# Power-Conversion.net
KiCad netlist of a schematic drawn in EAGLE
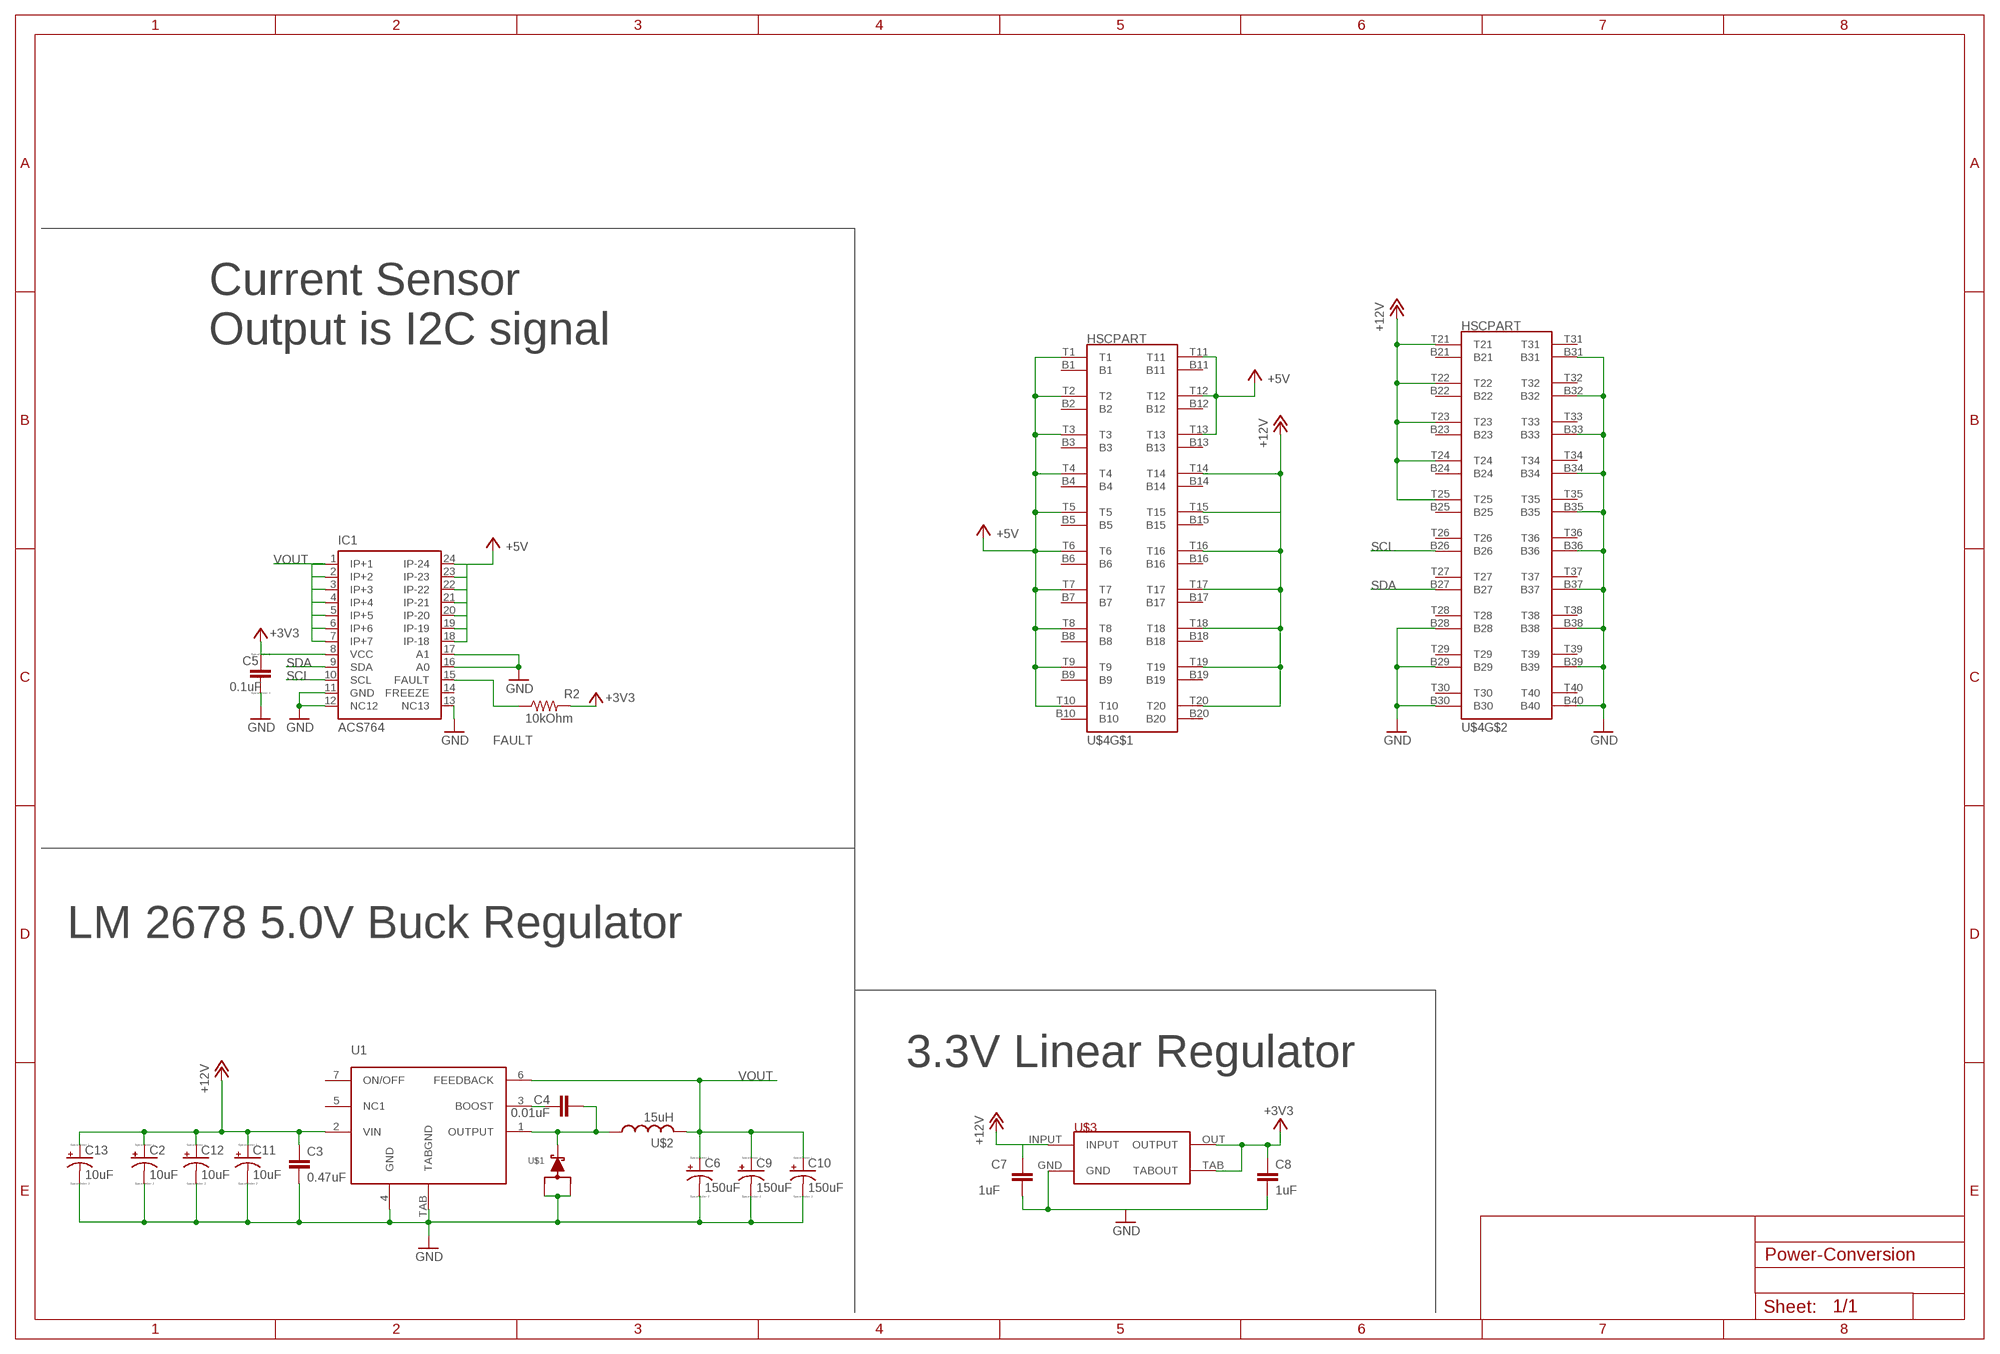
[diagram p0: schematic, sheet 1]

(export (version "E")
  (design (tool "Eeschema 10.0.6"))
  (components
    (comp (ref "C2")
      (value "10uF")
      (footprint "eagle-import:CTAN(7.30_4.30MM)")
      (libsource (lib "eagle-import") (part "C-TANTALUM(10UF_150UF)"))
    )
    (comp (ref "C3")
      (value "0.47uF")
      (footprint "eagle-import:0805")
      (libsource (lib "eagle-import") (part "CAP0805"))
    )
    (comp (ref "C4")
      (value "0.01uF")
      (footprint "eagle-import:0603-CAP")
      (libsource (lib "eagle-import") (part "SparkFun-Passives_CAP0603-CAP"))
    )
    (comp (ref "C5")
      (value "0.1uF")
      (footprint "eagle-import:C0603")
      (libsource (lib "eagle-import") (part "CC0603"))
    )
    (comp (ref "C6")
      (value "150uF")
      (footprint "eagle-import:CTAN(7.30_4.30MM)")
      (libsource (lib "eagle-import") (part "C-TANTALUM(10UF_150UF)"))
    )
    (comp (ref "C7")
      (value "1uF")
      (footprint "eagle-import:0603-CAP")
      (libsource (lib "eagle-import") (part "SparkFun-Passives_CAP0603-CAP"))
    )
    (comp (ref "C8")
      (value "1uF")
      (footprint "eagle-import:0603-CAP")
      (libsource (lib "eagle-import") (part "SparkFun-Passives_CAP0603-CAP"))
    )
    (comp (ref "C9")
      (value "150uF")
      (footprint "eagle-import:CTAN(7.30_4.30MM)")
      (libsource (lib "eagle-import") (part "C-TANTALUM(10UF_150UF)"))
    )
    (comp (ref "C10")
      (value "150uF")
      (footprint "eagle-import:CTAN(7.30_4.30MM)")
      (libsource (lib "eagle-import") (part "C-TANTALUM(10UF_150UF)"))
    )
    (comp (ref "C11")
      (value "10uF")
      (footprint "eagle-import:CTAN(7.30_4.30MM)")
      (libsource (lib "eagle-import") (part "C-TANTALUM(10UF_150UF)"))
    )
    (comp (ref "C12")
      (value "10uF")
      (footprint "eagle-import:CTAN(7.30_4.30MM)")
      (libsource (lib "eagle-import") (part "C-TANTALUM(10UF_150UF)"))
    )
    (comp (ref "C13")
      (value "10uF")
      (footprint "eagle-import:CTAN(7.30_4.30MM)")
      (libsource (lib "eagle-import") (part "C-TANTALUM(10UF_150UF)"))
    )
    (comp (ref "IC1")
      (value "ACS764")
      (footprint "eagle-import:SSOP24")
      (libsource (lib "eagle-import") (part "ACS764"))
    )
    (comp (ref "R2")
      (value "10kOhm")
      (footprint "eagle-import:R0603")
      (libsource (lib "eagle-import") (part "R-US_R0603"))
    )
    (comp (ref "U$1")
      (value "SWITCHMODE_SCHOTTKY")
      (footprint "eagle-import:DPAK-3")
      (libsource (lib "eagle-import") (part "SWITCHMODE_SCHOTTKY"))
    )
    (comp (ref "U$2")
      (value "15uH")
      (footprint "eagle-import:HCMA1305")
      (libsource (lib "eagle-import") (part "HCMA1305"))
    )
    (comp (ref "U$3")
      (value "NCP1117")
      (footprint "eagle-import:NCP1117")
      (libsource (lib "eagle-import") (part "NCP1117"))
    )
    (comp (ref "U$4")
      (value "HSCPART")
      (footprint "eagle-import:HSC8-40PINOUUT")
      (libsource (lib "eagle-import") (part "HSCPART"))
    )
    (comp (ref "U1")
      (value "LM2678")
      (footprint "eagle-import:LM2678")
      (libsource (lib "eagle-import") (part "LM2678"))
    )
  )
  (nets
    (net (code "1") (name "+3V3") (class "Default")
      (node (ref "C5") (pin "1") (pinfunction "1_1") (pintype "passive"))
      (node (ref "C8") (pin "1") (pinfunction "1_1") (pintype "passive"))
      (node (ref "IC1") (pin "8") (pinfunction "VCC_8") (pintype "bidirectional"))
      (node (ref "R2") (pin "2") (pinfunction "2_2") (pintype "passive"))
      (node (ref "U$3") (pin "OUT") (pinfunction "OUTPUT_OUT") (pintype "bidirectional"))
      (node (ref "U$3") (pin "TAB") (pinfunction "TABOUT_TAB") (pintype "bidirectional"))
    )
    (net (code "2") (name "+5V") (class "Default")
      (node (ref "IC1") (pin "18") (pinfunction "IP-18_18") (pintype "bidirectional"))
      (node (ref "IC1") (pin "19") (pinfunction "IP-19_19") (pintype "bidirectional"))
      (node (ref "IC1") (pin "20") (pinfunction "IP-20_20") (pintype "bidirectional"))
      (node (ref "IC1") (pin "21") (pinfunction "IP-21_21") (pintype "bidirectional"))
      (node (ref "IC1") (pin "22") (pinfunction "IP-22_22") (pintype "bidirectional"))
      (node (ref "IC1") (pin "23") (pinfunction "IP-23_23") (pintype "bidirectional"))
      (node (ref "IC1") (pin "24") (pinfunction "IP-24_24") (pintype "bidirectional"))
      (node (ref "U$4") (pin "T1") (pinfunction "T1_T1") (pintype "bidirectional"))
      (node (ref "U$4") (pin "T10") (pinfunction "T10_T10") (pintype "bidirectional"))
      (node (ref "U$4") (pin "T11") (pinfunction "T11_T11") (pintype "bidirectional"))
      (node (ref "U$4") (pin "T12") (pinfunction "T12_T12") (pintype "bidirectional"))
      (node (ref "U$4") (pin "T13") (pinfunction "T13_T13") (pintype "bidirectional"))
      (node (ref "U$4") (pin "T2") (pinfunction "T2_T2") (pintype "bidirectional"))
      (node (ref "U$4") (pin "T3") (pinfunction "T3_T3") (pintype "bidirectional"))
      (node (ref "U$4") (pin "T4") (pinfunction "T4_T4") (pintype "bidirectional"))
      (node (ref "U$4") (pin "T5") (pinfunction "T5_T5") (pintype "bidirectional"))
      (node (ref "U$4") (pin "T6") (pinfunction "T6_T6") (pintype "bidirectional"))
      (node (ref "U$4") (pin "T7") (pinfunction "T7_T7") (pintype "bidirectional"))
      (node (ref "U$4") (pin "T8") (pinfunction "T8_T8") (pintype "bidirectional"))
      (node (ref "U$4") (pin "T9") (pinfunction "T9_T9") (pintype "bidirectional"))
    )
    (net (code "3") (name "+12V") (class "Default")
      (node (ref "C11") (pin "+") (pinfunction "+_+") (pintype "passive"))
      (node (ref "C12") (pin "+") (pinfunction "+_+") (pintype "passive"))
      (node (ref "C13") (pin "+") (pinfunction "+_+") (pintype "passive"))
      (node (ref "C2") (pin "+") (pinfunction "+_+") (pintype "passive"))
      (node (ref "C3") (pin "1") (pinfunction "1_1") (pintype "passive"))
      (node (ref "C7") (pin "1") (pinfunction "1_1") (pintype "passive"))
      (node (ref "U$3") (pin "INPUT") (pinfunction "INPUT_INPUT") (pintype "bidirectional"))
      (node (ref "U$4") (pin "T14") (pinfunction "T14_T14") (pintype "bidirectional"))
      (node (ref "U$4") (pin "T15") (pinfunction "T15_T15") (pintype "bidirectional"))
      (node (ref "U$4") (pin "T16") (pinfunction "T16_T16") (pintype "bidirectional"))
      (node (ref "U$4") (pin "T17") (pinfunction "T17_T17") (pintype "bidirectional"))
      (node (ref "U$4") (pin "T18") (pinfunction "T18_T18") (pintype "bidirectional"))
      (node (ref "U$4") (pin "T19") (pinfunction "T19_T19") (pintype "bidirectional"))
      (node (ref "U$4") (pin "T20") (pinfunction "T20_T20") (pintype "bidirectional"))
      (node (ref "U$4") (pin "T21") (pinfunction "T21_T21") (pintype "bidirectional"))
      (node (ref "U$4") (pin "T22") (pinfunction "T22_T22") (pintype "bidirectional"))
      (node (ref "U$4") (pin "T23") (pinfunction "T23_T23") (pintype "bidirectional"))
      (node (ref "U$4") (pin "T24") (pinfunction "T24_T24") (pintype "bidirectional"))
      (node (ref "U$4") (pin "T25") (pinfunction "T25_T25") (pintype "bidirectional"))
      (node (ref "U1") (pin "2") (pinfunction "VIN_2") (pintype "bidirectional"))
    )
    (net (code "4") (name "/FAULT") (class "Default")
      (node (ref "IC1") (pin "15") (pinfunction "FAULT_15") (pintype "bidirectional"))
      (node (ref "R2") (pin "1") (pinfunction "1_1") (pintype "passive"))
    )
    (net (code "5") (name "/SCL") (class "Default")
      (node (ref "IC1") (pin "10") (pinfunction "SCL_10") (pintype "bidirectional"))
      (node (ref "U$4") (pin "B26") (pinfunction "B26_B26") (pintype "bidirectional"))
    )
    (net (code "6") (name "/SDA") (class "Default")
      (node (ref "IC1") (pin "9") (pinfunction "SDA_9") (pintype "bidirectional"))
      (node (ref "U$4") (pin "B27") (pinfunction "B27_B27") (pintype "bidirectional"))
    )
    (net (code "7") (name "/VOUT") (class "Default")
      (node (ref "C10") (pin "+") (pinfunction "+_+") (pintype "passive"))
      (node (ref "C6") (pin "+") (pinfunction "+_+") (pintype "passive"))
      (node (ref "C9") (pin "+") (pinfunction "+_+") (pintype "passive"))
      (node (ref "IC1") (pin "1") (pinfunction "IP+1_1") (pintype "bidirectional"))
      (node (ref "IC1") (pin "2") (pinfunction "IP+2_2") (pintype "bidirectional"))
      (node (ref "IC1") (pin "3") (pinfunction "IP+3_3") (pintype "bidirectional"))
      (node (ref "IC1") (pin "4") (pinfunction "IP+4_4") (pintype "bidirectional"))
      (node (ref "IC1") (pin "5") (pinfunction "IP+5_5") (pintype "bidirectional"))
      (node (ref "IC1") (pin "6") (pinfunction "IP+6_6") (pintype "bidirectional"))
      (node (ref "IC1") (pin "7") (pinfunction "IP+7_7") (pintype "bidirectional"))
      (node (ref "U$2") (pin "P$2") (pinfunction "2_P$2") (pintype "passive"))
      (node (ref "U1") (pin "6") (pinfunction "FEEDBACK_6") (pintype "bidirectional"))
    )
    (net (code "8") (name "GND") (class "Default")
      (node (ref "C10") (pin "-") (pinfunction "-_-") (pintype "passive"))
      (node (ref "C11") (pin "-") (pinfunction "-_-") (pintype "passive"))
      (node (ref "C12") (pin "-") (pinfunction "-_-") (pintype "passive"))
      (node (ref "C13") (pin "-") (pinfunction "-_-") (pintype "passive"))
      (node (ref "C2") (pin "-") (pinfunction "-_-") (pintype "passive"))
      (node (ref "C3") (pin "2") (pinfunction "2_2") (pintype "passive"))
      (node (ref "C5") (pin "2") (pinfunction "2_2") (pintype "passive"))
      (node (ref "C6") (pin "-") (pinfunction "-_-") (pintype "passive"))
      (node (ref "C7") (pin "2") (pinfunction "2_2") (pintype "passive"))
      (node (ref "C8") (pin "2") (pinfunction "2_2") (pintype "passive"))
      (node (ref "C9") (pin "-") (pinfunction "-_-") (pintype "passive"))
      (node (ref "IC1") (pin "11") (pinfunction "GND_11") (pintype "bidirectional"))
      (node (ref "IC1") (pin "12") (pinfunction "NC12_12") (pintype "bidirectional"))
      (node (ref "IC1") (pin "13") (pinfunction "NC13_13") (pintype "bidirectional"))
      (node (ref "IC1") (pin "16") (pinfunction "A0_16") (pintype "bidirectional"))
      (node (ref "IC1") (pin "17") (pinfunction "A1_17") (pintype "bidirectional"))
      (node (ref "U$1") (pin "P$1") (pinfunction "P$1_P$1") (pintype "bidirectional"))
      (node (ref "U$1") (pin "P$3") (pinfunction "P$3_P$3") (pintype "bidirectional"))
      (node (ref "U$3") (pin "GND") (pinfunction "GND_GND") (pintype "bidirectional"))
      (node (ref "U$4") (pin "B28") (pinfunction "B28_B28") (pintype "bidirectional"))
      (node (ref "U$4") (pin "B29") (pinfunction "B29_B29") (pintype "bidirectional"))
      (node (ref "U$4") (pin "B30") (pinfunction "B30_B30") (pintype "bidirectional"))
      (node (ref "U$4") (pin "B31") (pinfunction "B31_B31") (pintype "bidirectional"))
      (node (ref "U$4") (pin "B32") (pinfunction "B32_B32") (pintype "bidirectional"))
      (node (ref "U$4") (pin "B33") (pinfunction "B33_B33") (pintype "bidirectional"))
      (node (ref "U$4") (pin "B34") (pinfunction "B34_B34") (pintype "bidirectional"))
      (node (ref "U$4") (pin "B35") (pinfunction "B35_B35") (pintype "bidirectional"))
      (node (ref "U$4") (pin "B36") (pinfunction "B36_B36") (pintype "bidirectional"))
      (node (ref "U$4") (pin "B37") (pinfunction "B37_B37") (pintype "bidirectional"))
      (node (ref "U$4") (pin "B38") (pinfunction "B38_B38") (pintype "bidirectional"))
      (node (ref "U$4") (pin "B39") (pinfunction "B39_B39") (pintype "bidirectional"))
      (node (ref "U$4") (pin "B40") (pinfunction "B40_B40") (pintype "bidirectional"))
      (node (ref "U1") (pin "4") (pinfunction "GND_4") (pintype "bidirectional"))
      (node (ref "U1") (pin "TAB") (pinfunction "TABGND_TAB") (pintype "bidirectional"))
    )
    (net (code "9") (name "Net-(U$2-1)") (class "Default")
      (node (ref "C4") (pin "2") (pinfunction "2_2") (pintype "passive"))
      (node (ref "U$1") (pin "P$4") (pinfunction "P$4_P$4") (pintype "bidirectional"))
      (node (ref "U$2") (pin "P$1") (pinfunction "1_P$1") (pintype "passive"))
      (node (ref "U1") (pin "1") (pinfunction "OUTPUT_1") (pintype "bidirectional"))
    )
    (net (code "10") (name "Net-(U1-BOOST)") (class "Default")
      (node (ref "C4") (pin "1") (pinfunction "1_1") (pintype "passive"))
      (node (ref "U1") (pin "3") (pinfunction "BOOST_3") (pintype "bidirectional"))
    )
    (net (code "11") (name "unconnected-(IC1-FREEZE-Pad14)") (class "Default")
      (node (ref "IC1") (pin "14") (pinfunction "FREEZE_14") (pintype "bidirectional"))
    )
    (net (code "12") (name "unconnected-(U$4-PadB1)") (class "Default")
      (node (ref "U$4") (pin "B1") (pinfunction "B1_B1") (pintype "bidirectional"))
    )
    (net (code "13") (name "unconnected-(U$4-PadB2)") (class "Default")
      (node (ref "U$4") (pin "B2") (pinfunction "B2_B2") (pintype "bidirectional"))
    )
    (net (code "14") (name "unconnected-(U$4-PadB3)") (class "Default")
      (node (ref "U$4") (pin "B3") (pinfunction "B3_B3") (pintype "bidirectional"))
    )
    (net (code "15") (name "unconnected-(U$4-PadB4)") (class "Default")
      (node (ref "U$4") (pin "B4") (pinfunction "B4_B4") (pintype "bidirectional"))
    )
    (net (code "16") (name "unconnected-(U$4-PadB5)") (class "Default")
      (node (ref "U$4") (pin "B5") (pinfunction "B5_B5") (pintype "bidirectional"))
    )
    (net (code "17") (name "unconnected-(U$4-PadB6)") (class "Default")
      (node (ref "U$4") (pin "B6") (pinfunction "B6_B6") (pintype "bidirectional"))
    )
    (net (code "18") (name "unconnected-(U$4-PadB7)") (class "Default")
      (node (ref "U$4") (pin "B7") (pinfunction "B7_B7") (pintype "bidirectional"))
    )
    (net (code "19") (name "unconnected-(U$4-PadB8)") (class "Default")
      (node (ref "U$4") (pin "B8") (pinfunction "B8_B8") (pintype "bidirectional"))
    )
    (net (code "20") (name "unconnected-(U$4-PadB9)") (class "Default")
      (node (ref "U$4") (pin "B9") (pinfunction "B9_B9") (pintype "bidirectional"))
    )
    (net (code "21") (name "unconnected-(U$4-PadB10)") (class "Default")
      (node (ref "U$4") (pin "B10") (pinfunction "B10_B10") (pintype "bidirectional"))
    )
    (net (code "22") (name "unconnected-(U$4-PadB11)") (class "Default")
      (node (ref "U$4") (pin "B11") (pinfunction "B11_B11") (pintype "bidirectional"))
    )
    (net (code "23") (name "unconnected-(U$4-PadB12)") (class "Default")
      (node (ref "U$4") (pin "B12") (pinfunction "B12_B12") (pintype "bidirectional"))
    )
    (net (code "24") (name "unconnected-(U$4-PadB13)") (class "Default")
      (node (ref "U$4") (pin "B13") (pinfunction "B13_B13") (pintype "bidirectional"))
    )
    (net (code "25") (name "unconnected-(U$4-PadB14)") (class "Default")
      (node (ref "U$4") (pin "B14") (pinfunction "B14_B14") (pintype "bidirectional"))
    )
    (net (code "26") (name "unconnected-(U$4-PadB15)") (class "Default")
      (node (ref "U$4") (pin "B15") (pinfunction "B15_B15") (pintype "bidirectional"))
    )
    (net (code "27") (name "unconnected-(U$4-PadB16)") (class "Default")
      (node (ref "U$4") (pin "B16") (pinfunction "B16_B16") (pintype "bidirectional"))
    )
    (net (code "28") (name "unconnected-(U$4-PadB17)") (class "Default")
      (node (ref "U$4") (pin "B17") (pinfunction "B17_B17") (pintype "bidirectional"))
    )
    (net (code "29") (name "unconnected-(U$4-PadB18)") (class "Default")
      (node (ref "U$4") (pin "B18") (pinfunction "B18_B18") (pintype "bidirectional"))
    )
    (net (code "30") (name "unconnected-(U$4-PadB19)") (class "Default")
      (node (ref "U$4") (pin "B19") (pinfunction "B19_B19") (pintype "bidirectional"))
    )
    (net (code "31") (name "unconnected-(U$4-PadB20)") (class "Default")
      (node (ref "U$4") (pin "B20") (pinfunction "B20_B20") (pintype "bidirectional"))
    )
    (net (code "32") (name "unconnected-(U$4-PadB21)") (class "Default")
      (node (ref "U$4") (pin "B21") (pinfunction "B21_B21") (pintype "bidirectional"))
    )
    (net (code "33") (name "unconnected-(U$4-PadB22)") (class "Default")
      (node (ref "U$4") (pin "B22") (pinfunction "B22_B22") (pintype "bidirectional"))
    )
    (net (code "34") (name "unconnected-(U$4-PadB23)") (class "Default")
      (node (ref "U$4") (pin "B23") (pinfunction "B23_B23") (pintype "bidirectional"))
    )
    (net (code "35") (name "unconnected-(U$4-PadB24)") (class "Default")
      (node (ref "U$4") (pin "B24") (pinfunction "B24_B24") (pintype "bidirectional"))
    )
    (net (code "36") (name "unconnected-(U$4-PadB25)") (class "Default")
      (node (ref "U$4") (pin "B25") (pinfunction "B25_B25") (pintype "bidirectional"))
    )
    (net (code "37") (name "unconnected-(U$4-PadT26)") (class "Default")
      (node (ref "U$4") (pin "T26") (pinfunction "T26_T26") (pintype "bidirectional"))
    )
    (net (code "38") (name "unconnected-(U$4-PadT27)") (class "Default")
      (node (ref "U$4") (pin "T27") (pinfunction "T27_T27") (pintype "bidirectional"))
    )
    (net (code "39") (name "unconnected-(U$4-PadT28)") (class "Default")
      (node (ref "U$4") (pin "T28") (pinfunction "T28_T28") (pintype "bidirectional"))
    )
    (net (code "40") (name "unconnected-(U$4-PadT29)") (class "Default")
      (node (ref "U$4") (pin "T29") (pinfunction "T29_T29") (pintype "bidirectional"))
    )
    (net (code "41") (name "unconnected-(U$4-PadT30)") (class "Default")
      (node (ref "U$4") (pin "T30") (pinfunction "T30_T30") (pintype "bidirectional"))
    )
    (net (code "42") (name "unconnected-(U$4-PadT31)") (class "Default")
      (node (ref "U$4") (pin "T31") (pinfunction "T31_T31") (pintype "bidirectional"))
    )
    (net (code "43") (name "unconnected-(U$4-PadT32)") (class "Default")
      (node (ref "U$4") (pin "T32") (pinfunction "T32_T32") (pintype "bidirectional"))
    )
    (net (code "44") (name "unconnected-(U$4-PadT33)") (class "Default")
      (node (ref "U$4") (pin "T33") (pinfunction "T33_T33") (pintype "bidirectional"))
    )
    (net (code "45") (name "unconnected-(U$4-PadT34)") (class "Default")
      (node (ref "U$4") (pin "T34") (pinfunction "T34_T34") (pintype "bidirectional"))
    )
    (net (code "46") (name "unconnected-(U$4-PadT35)") (class "Default")
      (node (ref "U$4") (pin "T35") (pinfunction "T35_T35") (pintype "bidirectional"))
    )
    (net (code "47") (name "unconnected-(U$4-PadT36)") (class "Default")
      (node (ref "U$4") (pin "T36") (pinfunction "T36_T36") (pintype "bidirectional"))
    )
    (net (code "48") (name "unconnected-(U$4-PadT37)") (class "Default")
      (node (ref "U$4") (pin "T37") (pinfunction "T37_T37") (pintype "bidirectional"))
    )
    (net (code "49") (name "unconnected-(U$4-PadT38)") (class "Default")
      (node (ref "U$4") (pin "T38") (pinfunction "T38_T38") (pintype "bidirectional"))
    )
    (net (code "50") (name "unconnected-(U$4-PadT39)") (class "Default")
      (node (ref "U$4") (pin "T39") (pinfunction "T39_T39") (pintype "bidirectional"))
    )
    (net (code "51") (name "unconnected-(U$4-PadT40)") (class "Default")
      (node (ref "U$4") (pin "T40") (pinfunction "T40_T40") (pintype "bidirectional"))
    )
    (net (code "52") (name "unconnected-(U1-NC1-Pad5)") (class "Default")
      (node (ref "U1") (pin "5") (pinfunction "NC1_5") (pintype "no_connect"))
    )
    (net (code "53") (name "unconnected-(U1-ON{slash}OFF-Pad7)") (class "Default")
      (node (ref "U1") (pin "7") (pinfunction "ON/OFF_7") (pintype "bidirectional"))
    )
  )
)
